# CZ100_V1_0.net
KiCad netlist of a schematic drawn in Altium Designer
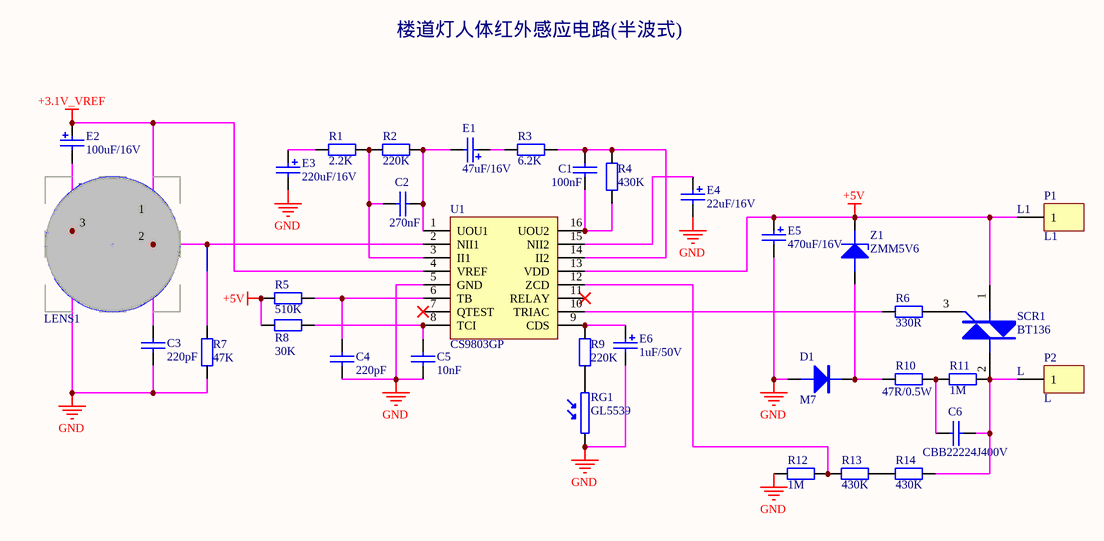
[diagram p0: CZ100_V1.0.SchDoc]

(export (version "E")
  (design (tool "Eeschema 10.0.6"))
  (components
    (comp (ref "C1")
      (value "100nF")
      (footprint "Cheng_Resistor_Capacitor:0805_C1")
      (libsource (lib "Cheng_Resistor_Capacitor") (part "Cap1"))
    )
    (comp (ref "C2")
      (value "270nF")
      (footprint "Cheng_Resistor_Capacitor:0805_C1")
      (libsource (lib "Cheng_Resistor_Capacitor") (part "Cap1"))
    )
    (comp (ref "C3")
      (value "220pF")
      (footprint "Cheng_Resistor_Capacitor:0805_C1")
      (libsource (lib "Cheng_Resistor_Capacitor") (part "Cap1"))
    )
    (comp (ref "C4")
      (value "220pF")
      (footprint "Cheng_Resistor_Capacitor:0805_C1")
      (libsource (lib "Cheng_Resistor_Capacitor") (part "Cap1"))
    )
    (comp (ref "C5")
      (value "10nF")
      (footprint "Cheng_Resistor_Capacitor:0805_C1")
      (libsource (lib "Cheng_Resistor_Capacitor") (part "Cap1"))
    )
    (comp (ref "C6")
      (value "CBB22224J400V")
      (footprint "Cheng_Resistor_Capacitor:CBB22224J400V")
      (libsource (lib "Cheng_Resistor_Capacitor") (part "Cap1"))
    )
    (comp (ref "D1")
      (value "M7")
      (footprint "Cheng_Diode_Transistor:DO-214AC(SMA)")
      (description "SS14,SS24,SS34,M7")
      (libsource (lib "Cheng_Diode_Transistor") (part "Diode-A"))
    )
    (comp (ref "E1")
      (value "47uF/16V")
      (footprint "Cheng_Resistor_Capacitor:CS_47uF/25V")
      (libsource (lib "Cheng_Resistor_Capacitor") (part "Cap Pol1"))
    )
    (comp (ref "E2")
      (value "100uF/16V")
      (footprint "Cheng_Resistor_Capacitor:CS_100uF/16V")
      (libsource (lib "Cheng_Resistor_Capacitor") (part "Cap Pol1"))
    )
    (comp (ref "E3")
      (value "220uF/16V")
      (footprint "Cheng_Resistor_Capacitor:CS_220uF/16V")
      (libsource (lib "Cheng_Resistor_Capacitor") (part "Cap Pol1"))
    )
    (comp (ref "E4")
      (value "22uF/16V")
      (footprint "Cheng_Resistor_Capacitor:CS_47uF/25V")
      (libsource (lib "Cheng_Resistor_Capacitor") (part "Cap Pol1"))
    )
    (comp (ref "E5")
      (value "470uF/16V")
      (footprint "Cheng_Resistor_Capacitor:CS_470uF/16V")
      (libsource (lib "Cheng_Resistor_Capacitor") (part "Cap Pol1"))
    )
    (comp (ref "E6")
      (value "1uF/50V")
      (footprint "Cheng_Resistor_Capacitor:CS_47uF/25V")
      (libsource (lib "Cheng_Resistor_Capacitor") (part "Cap Pol1"))
    )
    (comp (ref "LENS1")
      (value "Fresnel lens")
      (footprint "Cheng_Misc Component:Fresnel lens")
      (libsource (lib "Cheng_Misc Component") (part "Fresnel lens"))
    )
    (comp (ref "P1")
      (value "L1")
      (footprint "Cheng_Interface Unit:CP3M*8.8")
      (description "Header, 1-Pin")
      (fields (field (name "PUBLISHER") "Altium Limited"))
      (libsource (lib "Cheng_Interface Unit") (part "Header 1"))
    )
    (comp (ref "P2")
      (value "L")
      (footprint "Cheng_Interface Unit:CP3M*8.8")
      (description "Header, 1-Pin")
      (fields (field (name "PUBLISHER") "Altium Limited"))
      (libsource (lib "Cheng_Interface Unit") (part "Header 1"))
    )
    (comp (ref "PRI1")
      (value "KP500BP")
      (footprint "D203S")
      (description "D203S, KP500BP")
      (libsource (lib "Cheng_IC") (part "D203S"))
    )
    (comp (ref "R1")
      (value "2.2K")
      (footprint "Cheng_Resistor_Capacitor:0805_R")
      (libsource (lib "") (part "Res1_1"))
    )
    (comp (ref "R2")
      (value "220K")
      (footprint "Cheng_Resistor_Capacitor:0805_R")
      (libsource (lib "") (part "Res1_1"))
    )
    (comp (ref "R3")
      (value "6.2K")
      (footprint "Cheng_Resistor_Capacitor:0805_R")
      (libsource (lib "Cheng_Resistor_Capacitor") (part "Res1"))
    )
    (comp (ref "R4")
      (value "430K")
      (footprint "Cheng_Resistor_Capacitor:0805_R")
      (libsource (lib "") (part "Res1_3"))
    )
    (comp (ref "R5")
      (value "510K")
      (footprint "Cheng_Resistor_Capacitor:0805_R")
      (libsource (lib "Cheng_Resistor_Capacitor") (part "Res1"))
    )
    (comp (ref "R6")
      (value "330R")
      (footprint "Cheng_Resistor_Capacitor:1206_R")
      (libsource (lib "") (part "Res1_1"))
    )
    (comp (ref "R7")
      (value "47K")
      (footprint "Cheng_Resistor_Capacitor:0805_R")
      (libsource (lib "") (part "Res1_2"))
    )
    (comp (ref "R8")
      (value "30K")
      (footprint "Cheng_Resistor_Capacitor:0805_R")
      (libsource (lib "Cheng_Resistor_Capacitor") (part "Res1"))
    )
    (comp (ref "R9")
      (value "220K")
      (footprint "Cheng_Resistor_Capacitor:0805_R")
      (libsource (lib "") (part "Res1_2"))
    )
    (comp (ref "R10")
      (value "47R/0.5W")
      (footprint "Cheng_Resistor_Capacitor:RT50")
      (libsource (lib "") (part "Res1_1"))
    )
    (comp (ref "R11")
      (value "1M")
      (footprint "Cheng_Resistor_Capacitor:1206_R")
      (libsource (lib "Cheng_Resistor_Capacitor") (part "Res1"))
    )
    (comp (ref "R12")
      (value "1M")
      (footprint "Cheng_Resistor_Capacitor:0805_R")
      (libsource (lib "Cheng_Resistor_Capacitor") (part "Res1"))
    )
    (comp (ref "R13")
      (value "430K")
      (footprint "Cheng_Resistor_Capacitor:1206_R")
      (libsource (lib "Cheng_Resistor_Capacitor") (part "Res1"))
    )
    (comp (ref "R14")
      (value "430K")
      (footprint "Cheng_Resistor_Capacitor:1206_R")
      (libsource (lib "") (part "Res1_1"))
    )
    (comp (ref "RG1")
      (value "GL5539")
      (footprint "Cheng_Resistor_Capacitor:R5537")
      (libsource (lib "Cheng_Resistor_Capacitor") (part "GL5539"))
    )
    (comp (ref "SCR1")
      (value "BT136")
      (footprint "Cheng_Manostat:TO-252")
      (libsource (lib "Cheng_Diode_Transistor") (part "TRIAC"))
    )
    (comp (ref "U1")
      (value "CS9803GP")
      (footprint "Cheng_IC:DIP-16")
      (libsource (lib "Cheng_IC") (part "CS9803GP"))
    )
    (comp (ref "Z1")
      (value "ZMM5V6")
      (footprint "Cheng_Diode_Transistor:LL-34")
      (libsource (lib "Cheng_Diode_Transistor") (part "Diode-B"))
    )
  )
  (nets
    (net (code "1") (name "+3.1V_VREF") (class "Default")
      (node (ref "E2") (pin "1") (pinfunction "1_1") (pintype "passive"))
      (node (ref "PRI1") (pin "1") (pinfunction "D_1") (pintype "passive"))
      (node (ref "U1") (pin "4") (pinfunction "VREF_4") (pintype "passive"))
    )
    (net (code "2") (name "+5V") (class "Default")
      (node (ref "E5") (pin "1") (pinfunction "1_1") (pintype "passive"))
      (node (ref "P1") (pin "1") (pinfunction "1_1") (pintype "passive"))
      (node (ref "R5") (pin "2") (pinfunction "2_2") (pintype "passive"))
      (node (ref "R8") (pin "2") (pinfunction "2_2") (pintype "passive"))
      (node (ref "SCR1") (pin "1") (pinfunction "T_1") (pintype "passive"))
      (node (ref "U1") (pin "13") (pinfunction "VDD_13") (pintype "passive"))
      (node (ref "Z1") (pin "K") (pinfunction "2_K") (pintype "passive"))
    )
    (net (code "3") (name "GND") (class "Default")
      (node (ref "C3") (pin "2") (pinfunction "2_2") (pintype "passive"))
      (node (ref "C4") (pin "2") (pinfunction "2_2") (pintype "passive"))
      (node (ref "C5") (pin "2") (pinfunction "2_2") (pintype "passive"))
      (node (ref "D1") (pin "A") (pinfunction "1_A") (pintype "passive"))
      (node (ref "E2") (pin "2") (pinfunction "2_2") (pintype "passive"))
      (node (ref "E3") (pin "2") (pinfunction "2_2") (pintype "passive"))
      (node (ref "E4") (pin "2") (pinfunction "2_2") (pintype "passive"))
      (node (ref "E5") (pin "2") (pinfunction "2_2") (pintype "passive"))
      (node (ref "E6") (pin "2") (pinfunction "2_2") (pintype "passive"))
      (node (ref "PRI1") (pin "3") (pinfunction "G_3") (pintype "passive"))
      (node (ref "R12") (pin "2") (pinfunction "2_2") (pintype "passive"))
      (node (ref "R7") (pin "1") (pinfunction "1_1") (pintype "passive"))
      (node (ref "RG1") (pin "1") (pinfunction "1_1") (pintype "passive"))
      (node (ref "U1") (pin "5") (pinfunction "GND_5") (pintype "passive"))
    )
    (net (code "4") (name "Net-(C6-Pad1)") (class "Default")
      (node (ref "C6") (pin "1") (pinfunction "1_1") (pintype "passive"))
      (node (ref "P2") (pin "1") (pinfunction "1_1") (pintype "passive"))
      (node (ref "R11") (pin "1") (pinfunction "1_1") (pintype "passive"))
      (node (ref "R14") (pin "2") (pinfunction "2_2") (pintype "passive"))
      (node (ref "SCR1") (pin "2") (pinfunction "T_2") (pintype "passive"))
    )
    (net (code "5") (name "Net-(C6-Pad2)") (class "Default")
      (node (ref "C6") (pin "2") (pinfunction "2_2") (pintype "passive"))
      (node (ref "R10") (pin "2") (pinfunction "2_2") (pintype "passive"))
      (node (ref "R11") (pin "2") (pinfunction "2_2") (pintype "passive"))
    )
    (net (code "6") (name "Net-(D1-2)") (class "Default")
      (node (ref "D1") (pin "K") (pinfunction "2_K") (pintype "passive"))
      (node (ref "R10") (pin "1") (pinfunction "1_1") (pintype "passive"))
      (node (ref "Z1") (pin "A") (pinfunction "1_A") (pintype "passive"))
    )
    (net (code "7") (name "Net-(E1-Pad1)") (class "Default")
      (node (ref "E1") (pin "1") (pinfunction "1_1") (pintype "passive"))
      (node (ref "R3") (pin "2") (pinfunction "2_2") (pintype "passive"))
    )
    (net (code "8") (name "Net-(E3-Pad1)") (class "Default")
      (node (ref "E3") (pin "1") (pinfunction "1_1") (pintype "passive"))
      (node (ref "R1") (pin "1") (pinfunction "1_1") (pintype "passive"))
    )
    (net (code "9") (name "Net-(PRI1-S)") (class "Default")
      (node (ref "C3") (pin "1") (pinfunction "1_1") (pintype "passive"))
      (node (ref "PRI1") (pin "2") (pinfunction "S_2") (pintype "passive"))
      (node (ref "R7") (pin "2") (pinfunction "2_2") (pintype "passive"))
      (node (ref "U1") (pin "2") (pinfunction "NII1_2") (pintype "passive"))
    )
    (net (code "10") (name "Net-(R9-Pad1)") (class "Default")
      (node (ref "R9") (pin "1") (pinfunction "1_1") (pintype "passive"))
      (node (ref "RG1") (pin "2") (pinfunction "2_2") (pintype "passive"))
    )
    (net (code "11") (name "Net-(R13-Pad1)") (class "Default")
      (node (ref "R13") (pin "1") (pinfunction "1_1") (pintype "passive"))
      (node (ref "R14") (pin "1") (pinfunction "1_1") (pintype "passive"))
    )
    (net (code "12") (name "Net-(SCR1-G)") (class "Default")
      (node (ref "R6") (pin "2") (pinfunction "2_2") (pintype "passive"))
      (node (ref "SCR1") (pin "3") (pinfunction "G_3") (pintype "passive"))
    )
    (net (code "13") (name "Net-(U1-CDS)") (class "Default")
      (node (ref "E6") (pin "1") (pinfunction "1_1") (pintype "passive"))
      (node (ref "R9") (pin "2") (pinfunction "2_2") (pintype "passive"))
      (node (ref "U1") (pin "9") (pinfunction "CDS_9") (pintype "passive"))
    )
    (net (code "14") (name "Net-(U1-II1)") (class "Default")
      (node (ref "C2") (pin "2") (pinfunction "2_2") (pintype "passive"))
      (node (ref "R1") (pin "2") (pinfunction "2_2") (pintype "passive"))
      (node (ref "R2") (pin "1") (pinfunction "1_1") (pintype "passive"))
      (node (ref "U1") (pin "3") (pinfunction "II1_3") (pintype "passive"))
    )
    (net (code "15") (name "Net-(U1-II2)") (class "Default")
      (node (ref "C1") (pin "2") (pinfunction "2_2") (pintype "passive"))
      (node (ref "R3") (pin "1") (pinfunction "1_1") (pintype "passive"))
      (node (ref "R4") (pin "1") (pinfunction "1_1") (pintype "passive"))
      (node (ref "U1") (pin "14") (pinfunction "II2_14") (pintype "passive"))
    )
    (net (code "16") (name "Net-(U1-NII2)") (class "Default")
      (node (ref "E4") (pin "1") (pinfunction "1_1") (pintype "passive"))
      (node (ref "U1") (pin "15") (pinfunction "NII2_15") (pintype "passive"))
    )
    (net (code "17") (name "Net-(U1-TB)") (class "Default")
      (node (ref "C4") (pin "1") (pinfunction "1_1") (pintype "passive"))
      (node (ref "R5") (pin "1") (pinfunction "1_1") (pintype "passive"))
      (node (ref "U1") (pin "6") (pinfunction "TB_6") (pintype "passive"))
    )
    (net (code "18") (name "Net-(U1-TCI)") (class "Default")
      (node (ref "C5") (pin "1") (pinfunction "1_1") (pintype "passive"))
      (node (ref "R8") (pin "1") (pinfunction "1_1") (pintype "passive"))
      (node (ref "U1") (pin "8") (pinfunction "TCI_8") (pintype "passive"))
    )
    (net (code "19") (name "Net-(U1-TRIAC)") (class "Default")
      (node (ref "R6") (pin "1") (pinfunction "1_1") (pintype "passive"))
      (node (ref "U1") (pin "10") (pinfunction "TRIAC_10") (pintype "passive"))
    )
    (net (code "20") (name "Net-(U1-UOU1)") (class "Default")
      (node (ref "C2") (pin "1") (pinfunction "1_1") (pintype "passive"))
      (node (ref "E1") (pin "2") (pinfunction "2_2") (pintype "passive"))
      (node (ref "R2") (pin "2") (pinfunction "2_2") (pintype "passive"))
      (node (ref "U1") (pin "1") (pinfunction "UOU1_1") (pintype "passive"))
    )
    (net (code "21") (name "Net-(U1-UOU2)") (class "Default")
      (node (ref "C1") (pin "1") (pinfunction "1_1") (pintype "passive"))
      (node (ref "R4") (pin "2") (pinfunction "2_2") (pintype "passive"))
      (node (ref "U1") (pin "16") (pinfunction "UOU2_16") (pintype "passive"))
    )
    (net (code "22") (name "Net-(U1-ZCD)") (class "Default")
      (node (ref "R12") (pin "1") (pinfunction "1_1") (pintype "passive"))
      (node (ref "R13") (pin "2") (pinfunction "2_2") (pintype "passive"))
      (node (ref "U1") (pin "12") (pinfunction "ZCD_12") (pintype "passive"))
    )
    (net (code "23") (name "unconnected-(U1-QTEST-Pad7)") (class "Default")
      (node (ref "U1") (pin "7") (pinfunction "QTEST_7") (pintype "passive+no_connect"))
    )
    (net (code "24") (name "unconnected-(U1-RELAY-Pad11)") (class "Default")
      (node (ref "U1") (pin "11") (pinfunction "RELAY_11") (pintype "passive+no_connect"))
    )
  )
)
